# SerialKeyboard.net
KiCad netlist of a schematic drawn in EAGLE
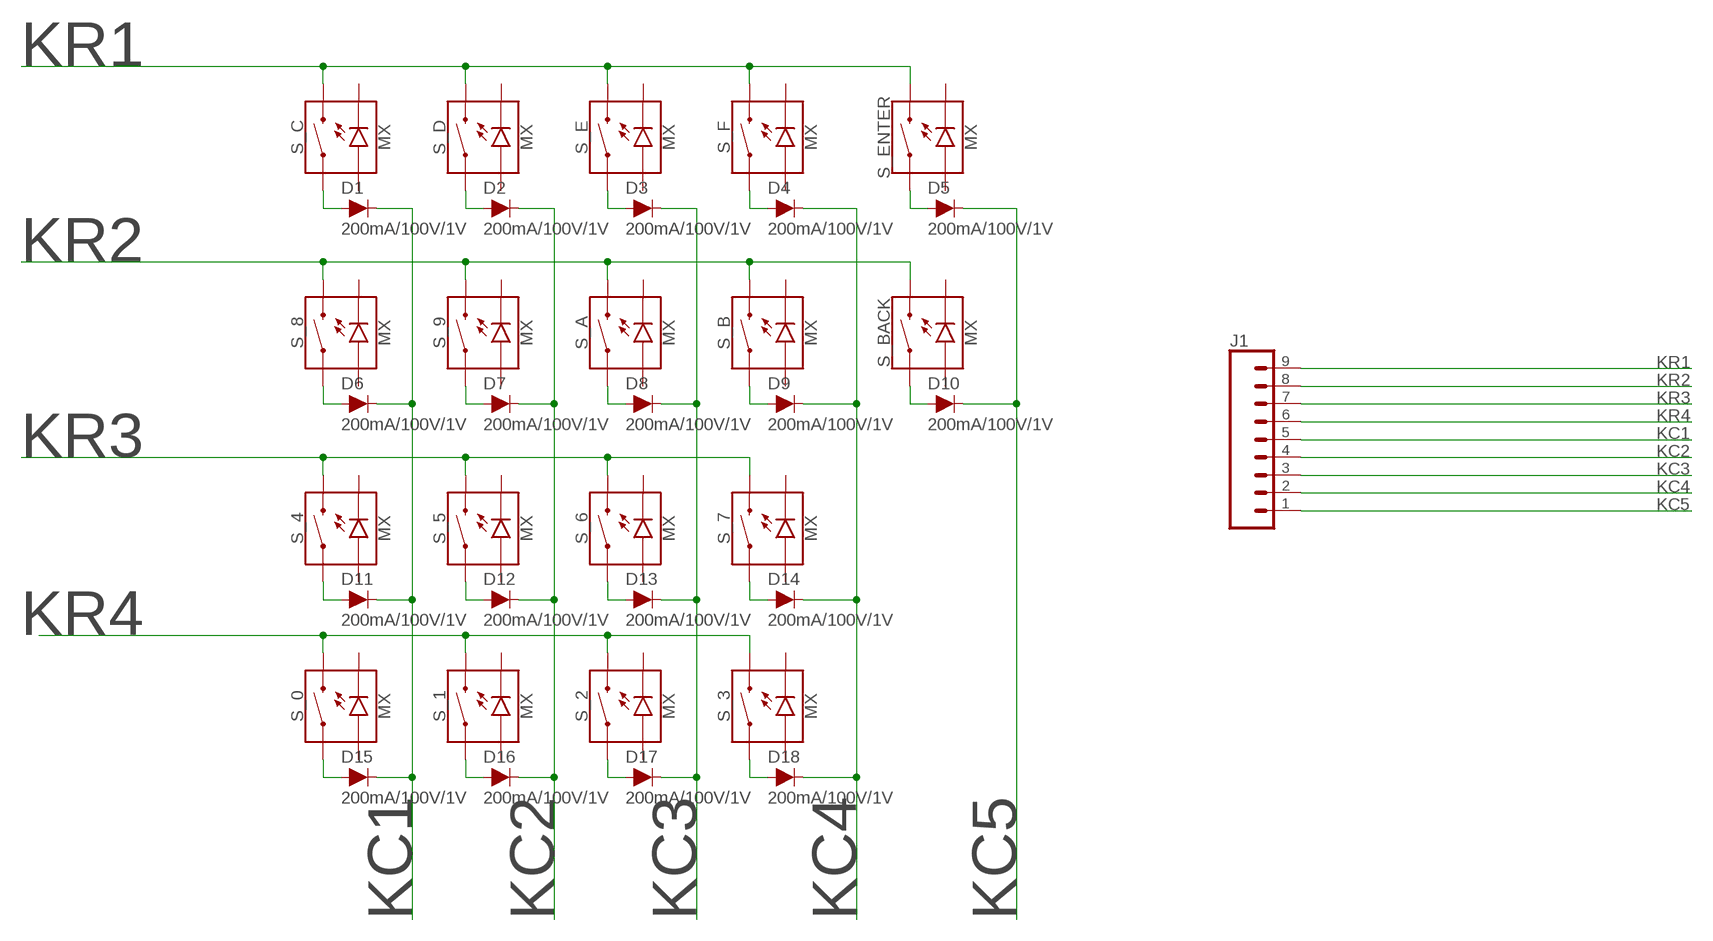
[diagram p0: schematic, sheet 1]

(export (version "E")
  (design (tool "Eeschema 10.0.6"))
  (components
    (comp (ref "D1")
      (value "200mA/100V/1V")
      (footprint "eagle-import:DIODE-1N4148")
      (libsource (lib "eagle-import") (part "DIODE-1N4148"))
    )
    (comp (ref "D2")
      (value "200mA/100V/1V")
      (footprint "eagle-import:DIODE-1N4148")
      (libsource (lib "eagle-import") (part "DIODE-1N4148"))
    )
    (comp (ref "D3")
      (value "200mA/100V/1V")
      (footprint "eagle-import:DIODE-1N4148")
      (libsource (lib "eagle-import") (part "DIODE-1N4148"))
    )
    (comp (ref "D4")
      (value "200mA/100V/1V")
      (footprint "eagle-import:DIODE-1N4148")
      (libsource (lib "eagle-import") (part "DIODE-1N4148"))
    )
    (comp (ref "D5")
      (value "200mA/100V/1V")
      (footprint "eagle-import:DIODE-1N4148")
      (libsource (lib "eagle-import") (part "DIODE-1N4148"))
    )
    (comp (ref "D6")
      (value "200mA/100V/1V")
      (footprint "eagle-import:DIODE-1N4148")
      (libsource (lib "eagle-import") (part "DIODE-1N4148"))
    )
    (comp (ref "D7")
      (value "200mA/100V/1V")
      (footprint "eagle-import:DIODE-1N4148")
      (libsource (lib "eagle-import") (part "DIODE-1N4148"))
    )
    (comp (ref "D8")
      (value "200mA/100V/1V")
      (footprint "eagle-import:DIODE-1N4148")
      (libsource (lib "eagle-import") (part "DIODE-1N4148"))
    )
    (comp (ref "D9")
      (value "200mA/100V/1V")
      (footprint "eagle-import:DIODE-1N4148")
      (libsource (lib "eagle-import") (part "DIODE-1N4148"))
    )
    (comp (ref "D10")
      (value "200mA/100V/1V")
      (footprint "eagle-import:DIODE-1N4148")
      (libsource (lib "eagle-import") (part "DIODE-1N4148"))
    )
    (comp (ref "D11")
      (value "200mA/100V/1V")
      (footprint "eagle-import:DIODE-1N4148")
      (libsource (lib "eagle-import") (part "DIODE-1N4148"))
    )
    (comp (ref "D12")
      (value "200mA/100V/1V")
      (footprint "eagle-import:DIODE-1N4148")
      (libsource (lib "eagle-import") (part "DIODE-1N4148"))
    )
    (comp (ref "D13")
      (value "200mA/100V/1V")
      (footprint "eagle-import:DIODE-1N4148")
      (libsource (lib "eagle-import") (part "DIODE-1N4148"))
    )
    (comp (ref "D14")
      (value "200mA/100V/1V")
      (footprint "eagle-import:DIODE-1N4148")
      (libsource (lib "eagle-import") (part "DIODE-1N4148"))
    )
    (comp (ref "D15")
      (value "200mA/100V/1V")
      (footprint "eagle-import:DIODE-1N4148")
      (libsource (lib "eagle-import") (part "DIODE-1N4148"))
    )
    (comp (ref "D16")
      (value "200mA/100V/1V")
      (footprint "eagle-import:DIODE-1N4148")
      (libsource (lib "eagle-import") (part "DIODE-1N4148"))
    )
    (comp (ref "D17")
      (value "200mA/100V/1V")
      (footprint "eagle-import:DIODE-1N4148")
      (libsource (lib "eagle-import") (part "DIODE-1N4148"))
    )
    (comp (ref "D18")
      (value "200mA/100V/1V")
      (footprint "eagle-import:DIODE-1N4148")
      (libsource (lib "eagle-import") (part "DIODE-1N4148"))
    )
    (comp (ref "J1")
      (value "CONN_09")
      (footprint "eagle-import:1X09")
      (libsource (lib "eagle-import") (part "CONN_09"))
    )
    (comp (ref "S_0")
      (value "MX")
      (footprint "eagle-import:CHERRY-MX-LED")
      (libsource (lib "eagle-import") (part "MOMENTARY-SWITCH-SPST-LED-PTH-CHERRY"))
    )
    (comp (ref "S_1")
      (value "MX")
      (footprint "eagle-import:CHERRY-MX-LED")
      (libsource (lib "eagle-import") (part "MOMENTARY-SWITCH-SPST-LED-PTH-CHERRY"))
    )
    (comp (ref "S_2")
      (value "MX")
      (footprint "eagle-import:CHERRY-MX-LED")
      (libsource (lib "eagle-import") (part "MOMENTARY-SWITCH-SPST-LED-PTH-CHERRY"))
    )
    (comp (ref "S_3")
      (value "MX")
      (footprint "eagle-import:CHERRY-MX-LED")
      (libsource (lib "eagle-import") (part "MOMENTARY-SWITCH-SPST-LED-PTH-CHERRY"))
    )
    (comp (ref "S_4")
      (value "MX")
      (footprint "eagle-import:CHERRY-MX-LED")
      (libsource (lib "eagle-import") (part "MOMENTARY-SWITCH-SPST-LED-PTH-CHERRY"))
    )
    (comp (ref "S_5")
      (value "MX")
      (footprint "eagle-import:CHERRY-MX-LED")
      (libsource (lib "eagle-import") (part "MOMENTARY-SWITCH-SPST-LED-PTH-CHERRY"))
    )
    (comp (ref "S_6")
      (value "MX")
      (footprint "eagle-import:CHERRY-MX-LED")
      (libsource (lib "eagle-import") (part "MOMENTARY-SWITCH-SPST-LED-PTH-CHERRY"))
    )
    (comp (ref "S_7")
      (value "MX")
      (footprint "eagle-import:CHERRY-MX-LED")
      (libsource (lib "eagle-import") (part "MOMENTARY-SWITCH-SPST-LED-PTH-CHERRY"))
    )
    (comp (ref "S_8")
      (value "MX")
      (footprint "eagle-import:CHERRY-MX-LED")
      (libsource (lib "eagle-import") (part "MOMENTARY-SWITCH-SPST-LED-PTH-CHERRY"))
    )
    (comp (ref "S_9")
      (value "MX")
      (footprint "eagle-import:CHERRY-MX-LED")
      (libsource (lib "eagle-import") (part "MOMENTARY-SWITCH-SPST-LED-PTH-CHERRY"))
    )
    (comp (ref "S_A")
      (value "MX")
      (footprint "eagle-import:CHERRY-MX-LED")
      (libsource (lib "eagle-import") (part "MOMENTARY-SWITCH-SPST-LED-PTH-CHERRY"))
    )
    (comp (ref "S_B")
      (value "MX")
      (footprint "eagle-import:CHERRY-MX-LED")
      (libsource (lib "eagle-import") (part "MOMENTARY-SWITCH-SPST-LED-PTH-CHERRY"))
    )
    (comp (ref "S_BACK")
      (value "MX")
      (footprint "eagle-import:CHERRY-MX-LED")
      (libsource (lib "eagle-import") (part "MOMENTARY-SWITCH-SPST-LED-PTH-CHERRY"))
    )
    (comp (ref "S_C")
      (value "MX")
      (footprint "eagle-import:CHERRY-MX-LED")
      (libsource (lib "eagle-import") (part "MOMENTARY-SWITCH-SPST-LED-PTH-CHERRY"))
    )
    (comp (ref "S_D")
      (value "MX")
      (footprint "eagle-import:CHERRY-MX-LED")
      (libsource (lib "eagle-import") (part "MOMENTARY-SWITCH-SPST-LED-PTH-CHERRY"))
    )
    (comp (ref "S_E")
      (value "MX")
      (footprint "eagle-import:CHERRY-MX-LED")
      (libsource (lib "eagle-import") (part "MOMENTARY-SWITCH-SPST-LED-PTH-CHERRY"))
    )
    (comp (ref "S_ENTER")
      (value "MX")
      (footprint "eagle-import:CHERRY-MX-LED")
      (libsource (lib "eagle-import") (part "MOMENTARY-SWITCH-SPST-LED-PTH-CHERRY"))
    )
    (comp (ref "S_F")
      (value "MX")
      (footprint "eagle-import:CHERRY-MX-LED")
      (libsource (lib "eagle-import") (part "MOMENTARY-SWITCH-SPST-LED-PTH-CHERRY"))
    )
  )
  (nets
    (net (code "1") (name "/KC1") (class "Default")
      (node (ref "D1") (pin "C") (pinfunction "C_C") (pintype "passive"))
      (node (ref "D11") (pin "C") (pinfunction "C_C") (pintype "passive"))
      (node (ref "D15") (pin "C") (pinfunction "C_C") (pintype "passive"))
      (node (ref "D6") (pin "C") (pinfunction "C_C") (pintype "passive"))
      (node (ref "J1") (pin "5") (pinfunction "5_5") (pintype "passive"))
    )
    (net (code "2") (name "/KC2") (class "Default")
      (node (ref "D12") (pin "C") (pinfunction "C_C") (pintype "passive"))
      (node (ref "D16") (pin "C") (pinfunction "C_C") (pintype "passive"))
      (node (ref "D2") (pin "C") (pinfunction "C_C") (pintype "passive"))
      (node (ref "D7") (pin "C") (pinfunction "C_C") (pintype "passive"))
      (node (ref "J1") (pin "4") (pinfunction "4_4") (pintype "passive"))
    )
    (net (code "3") (name "/KC3") (class "Default")
      (node (ref "D13") (pin "C") (pinfunction "C_C") (pintype "passive"))
      (node (ref "D17") (pin "C") (pinfunction "C_C") (pintype "passive"))
      (node (ref "D3") (pin "C") (pinfunction "C_C") (pintype "passive"))
      (node (ref "D8") (pin "C") (pinfunction "C_C") (pintype "passive"))
      (node (ref "J1") (pin "3") (pinfunction "3_3") (pintype "passive"))
    )
    (net (code "4") (name "/KC4") (class "Default")
      (node (ref "D14") (pin "C") (pinfunction "C_C") (pintype "passive"))
      (node (ref "D18") (pin "C") (pinfunction "C_C") (pintype "passive"))
      (node (ref "D4") (pin "C") (pinfunction "C_C") (pintype "passive"))
      (node (ref "D9") (pin "C") (pinfunction "C_C") (pintype "passive"))
      (node (ref "J1") (pin "2") (pinfunction "2_2") (pintype "passive"))
    )
    (net (code "5") (name "/KC5") (class "Default")
      (node (ref "D10") (pin "C") (pinfunction "C_C") (pintype "passive"))
      (node (ref "D5") (pin "C") (pinfunction "C_C") (pintype "passive"))
      (node (ref "J1") (pin "1") (pinfunction "1_1") (pintype "passive"))
    )
    (net (code "6") (name "/KR1") (class "Default")
      (node (ref "J1") (pin "9") (pinfunction "9_9") (pintype "passive"))
      (node (ref "S_C") (pin "S2") (pinfunction "2_S2") (pintype "passive"))
      (node (ref "S_D") (pin "S2") (pinfunction "2_S2") (pintype "passive"))
      (node (ref "S_E") (pin "S2") (pinfunction "2_S2") (pintype "passive"))
      (node (ref "S_ENTER") (pin "S2") (pinfunction "2_S2") (pintype "passive"))
      (node (ref "S_F") (pin "S2") (pinfunction "2_S2") (pintype "passive"))
    )
    (net (code "7") (name "/KR2") (class "Default")
      (node (ref "J1") (pin "8") (pinfunction "8_8") (pintype "passive"))
      (node (ref "S_8") (pin "S2") (pinfunction "2_S2") (pintype "passive"))
      (node (ref "S_9") (pin "S2") (pinfunction "2_S2") (pintype "passive"))
      (node (ref "S_A") (pin "S2") (pinfunction "2_S2") (pintype "passive"))
      (node (ref "S_B") (pin "S2") (pinfunction "2_S2") (pintype "passive"))
      (node (ref "S_BACK") (pin "S2") (pinfunction "2_S2") (pintype "passive"))
    )
    (net (code "8") (name "/KR3") (class "Default")
      (node (ref "J1") (pin "7") (pinfunction "7_7") (pintype "passive"))
      (node (ref "S_4") (pin "S2") (pinfunction "2_S2") (pintype "passive"))
      (node (ref "S_5") (pin "S2") (pinfunction "2_S2") (pintype "passive"))
      (node (ref "S_6") (pin "S2") (pinfunction "2_S2") (pintype "passive"))
      (node (ref "S_7") (pin "S2") (pinfunction "2_S2") (pintype "passive"))
    )
    (net (code "9") (name "/KR4") (class "Default")
      (node (ref "J1") (pin "6") (pinfunction "6_6") (pintype "passive"))
      (node (ref "S_0") (pin "S2") (pinfunction "2_S2") (pintype "passive"))
      (node (ref "S_1") (pin "S2") (pinfunction "2_S2") (pintype "passive"))
      (node (ref "S_2") (pin "S2") (pinfunction "2_S2") (pintype "passive"))
      (node (ref "S_3") (pin "S2") (pinfunction "2_S2") (pintype "passive"))
    )
    (net (code "10") (name "Net-(S_0-1)") (class "Default")
      (node (ref "D15") (pin "A") (pinfunction "A_A") (pintype "passive"))
      (node (ref "S_0") (pin "S1") (pinfunction "1_S1") (pintype "passive"))
    )
    (net (code "11") (name "Net-(S_1-1)") (class "Default")
      (node (ref "D16") (pin "A") (pinfunction "A_A") (pintype "passive"))
      (node (ref "S_1") (pin "S1") (pinfunction "1_S1") (pintype "passive"))
    )
    (net (code "12") (name "Net-(S_2-1)") (class "Default")
      (node (ref "D17") (pin "A") (pinfunction "A_A") (pintype "passive"))
      (node (ref "S_2") (pin "S1") (pinfunction "1_S1") (pintype "passive"))
    )
    (net (code "13") (name "Net-(S_3-1)") (class "Default")
      (node (ref "D18") (pin "A") (pinfunction "A_A") (pintype "passive"))
      (node (ref "S_3") (pin "S1") (pinfunction "1_S1") (pintype "passive"))
    )
    (net (code "14") (name "Net-(S_4-1)") (class "Default")
      (node (ref "D11") (pin "A") (pinfunction "A_A") (pintype "passive"))
      (node (ref "S_4") (pin "S1") (pinfunction "1_S1") (pintype "passive"))
    )
    (net (code "15") (name "Net-(S_5-1)") (class "Default")
      (node (ref "D12") (pin "A") (pinfunction "A_A") (pintype "passive"))
      (node (ref "S_5") (pin "S1") (pinfunction "1_S1") (pintype "passive"))
    )
    (net (code "16") (name "Net-(S_6-1)") (class "Default")
      (node (ref "D13") (pin "A") (pinfunction "A_A") (pintype "passive"))
      (node (ref "S_6") (pin "S1") (pinfunction "1_S1") (pintype "passive"))
    )
    (net (code "17") (name "Net-(S_7-1)") (class "Default")
      (node (ref "D14") (pin "A") (pinfunction "A_A") (pintype "passive"))
      (node (ref "S_7") (pin "S1") (pinfunction "1_S1") (pintype "passive"))
    )
    (net (code "18") (name "Net-(S_8-1)") (class "Default")
      (node (ref "D6") (pin "A") (pinfunction "A_A") (pintype "passive"))
      (node (ref "S_8") (pin "S1") (pinfunction "1_S1") (pintype "passive"))
    )
    (net (code "19") (name "Net-(S_9-1)") (class "Default")
      (node (ref "D7") (pin "A") (pinfunction "A_A") (pintype "passive"))
      (node (ref "S_9") (pin "S1") (pinfunction "1_S1") (pintype "passive"))
    )
    (net (code "20") (name "Net-(S_A-1)") (class "Default")
      (node (ref "D8") (pin "A") (pinfunction "A_A") (pintype "passive"))
      (node (ref "S_A") (pin "S1") (pinfunction "1_S1") (pintype "passive"))
    )
    (net (code "21") (name "Net-(S_B-1)") (class "Default")
      (node (ref "D9") (pin "A") (pinfunction "A_A") (pintype "passive"))
      (node (ref "S_B") (pin "S1") (pinfunction "1_S1") (pintype "passive"))
    )
    (net (code "22") (name "Net-(S_BACK-1)") (class "Default")
      (node (ref "D10") (pin "A") (pinfunction "A_A") (pintype "passive"))
      (node (ref "S_BACK") (pin "S1") (pinfunction "1_S1") (pintype "passive"))
    )
    (net (code "23") (name "Net-(S_C-1)") (class "Default")
      (node (ref "D1") (pin "A") (pinfunction "A_A") (pintype "passive"))
      (node (ref "S_C") (pin "S1") (pinfunction "1_S1") (pintype "passive"))
    )
    (net (code "24") (name "Net-(S_D-1)") (class "Default")
      (node (ref "D2") (pin "A") (pinfunction "A_A") (pintype "passive"))
      (node (ref "S_D") (pin "S1") (pinfunction "1_S1") (pintype "passive"))
    )
    (net (code "25") (name "Net-(S_E-1)") (class "Default")
      (node (ref "D3") (pin "A") (pinfunction "A_A") (pintype "passive"))
      (node (ref "S_E") (pin "S1") (pinfunction "1_S1") (pintype "passive"))
    )
    (net (code "26") (name "Net-(S_ENTER-1)") (class "Default")
      (node (ref "D5") (pin "A") (pinfunction "A_A") (pintype "passive"))
      (node (ref "S_ENTER") (pin "S1") (pinfunction "1_S1") (pintype "passive"))
    )
    (net (code "27") (name "Net-(S_F-1)") (class "Default")
      (node (ref "D4") (pin "A") (pinfunction "A_A") (pintype "passive"))
      (node (ref "S_F") (pin "S1") (pinfunction "1_S1") (pintype "passive"))
    )
    (net (code "28") (name "unconnected-(S_0-C-PadK)") (class "Default")
      (node (ref "S_0") (pin "K") (pinfunction "C_K") (pintype "passive"))
    )
    (net (code "29") (name "unconnected-(S_0-PadA)") (class "Default")
      (node (ref "S_0") (pin "A") (pinfunction "A_A") (pintype "passive"))
    )
    (net (code "30") (name "unconnected-(S_1-C-PadK)") (class "Default")
      (node (ref "S_1") (pin "K") (pinfunction "C_K") (pintype "passive"))
    )
    (net (code "31") (name "unconnected-(S_1-PadA)") (class "Default")
      (node (ref "S_1") (pin "A") (pinfunction "A_A") (pintype "passive"))
    )
    (net (code "32") (name "unconnected-(S_2-C-PadK)") (class "Default")
      (node (ref "S_2") (pin "K") (pinfunction "C_K") (pintype "passive"))
    )
    (net (code "33") (name "unconnected-(S_2-PadA)") (class "Default")
      (node (ref "S_2") (pin "A") (pinfunction "A_A") (pintype "passive"))
    )
    (net (code "34") (name "unconnected-(S_3-C-PadK)") (class "Default")
      (node (ref "S_3") (pin "K") (pinfunction "C_K") (pintype "passive"))
    )
    (net (code "35") (name "unconnected-(S_3-PadA)") (class "Default")
      (node (ref "S_3") (pin "A") (pinfunction "A_A") (pintype "passive"))
    )
    (net (code "36") (name "unconnected-(S_4-C-PadK)") (class "Default")
      (node (ref "S_4") (pin "K") (pinfunction "C_K") (pintype "passive"))
    )
    (net (code "37") (name "unconnected-(S_4-PadA)") (class "Default")
      (node (ref "S_4") (pin "A") (pinfunction "A_A") (pintype "passive"))
    )
    (net (code "38") (name "unconnected-(S_5-C-PadK)") (class "Default")
      (node (ref "S_5") (pin "K") (pinfunction "C_K") (pintype "passive"))
    )
    (net (code "39") (name "unconnected-(S_5-PadA)") (class "Default")
      (node (ref "S_5") (pin "A") (pinfunction "A_A") (pintype "passive"))
    )
    (net (code "40") (name "unconnected-(S_6-C-PadK)") (class "Default")
      (node (ref "S_6") (pin "K") (pinfunction "C_K") (pintype "passive"))
    )
    (net (code "41") (name "unconnected-(S_6-PadA)") (class "Default")
      (node (ref "S_6") (pin "A") (pinfunction "A_A") (pintype "passive"))
    )
    (net (code "42") (name "unconnected-(S_7-C-PadK)") (class "Default")
      (node (ref "S_7") (pin "K") (pinfunction "C_K") (pintype "passive"))
    )
    (net (code "43") (name "unconnected-(S_7-PadA)") (class "Default")
      (node (ref "S_7") (pin "A") (pinfunction "A_A") (pintype "passive"))
    )
    (net (code "44") (name "unconnected-(S_8-C-PadK)") (class "Default")
      (node (ref "S_8") (pin "K") (pinfunction "C_K") (pintype "passive"))
    )
    (net (code "45") (name "unconnected-(S_8-PadA)") (class "Default")
      (node (ref "S_8") (pin "A") (pinfunction "A_A") (pintype "passive"))
    )
    (net (code "46") (name "unconnected-(S_9-C-PadK)") (class "Default")
      (node (ref "S_9") (pin "K") (pinfunction "C_K") (pintype "passive"))
    )
    (net (code "47") (name "unconnected-(S_9-PadA)") (class "Default")
      (node (ref "S_9") (pin "A") (pinfunction "A_A") (pintype "passive"))
    )
    (net (code "48") (name "unconnected-(S_A-C-PadK)") (class "Default")
      (node (ref "S_A") (pin "K") (pinfunction "C_K") (pintype "passive"))
    )
    (net (code "49") (name "unconnected-(S_A-PadA)") (class "Default")
      (node (ref "S_A") (pin "A") (pinfunction "A_A") (pintype "passive"))
    )
    (net (code "50") (name "unconnected-(S_B-C-PadK)") (class "Default")
      (node (ref "S_B") (pin "K") (pinfunction "C_K") (pintype "passive"))
    )
    (net (code "51") (name "unconnected-(S_B-PadA)") (class "Default")
      (node (ref "S_B") (pin "A") (pinfunction "A_A") (pintype "passive"))
    )
    (net (code "52") (name "unconnected-(S_BACK-C-PadK)") (class "Default")
      (node (ref "S_BACK") (pin "K") (pinfunction "C_K") (pintype "passive"))
    )
    (net (code "53") (name "unconnected-(S_BACK-PadA)") (class "Default")
      (node (ref "S_BACK") (pin "A") (pinfunction "A_A") (pintype "passive"))
    )
    (net (code "54") (name "unconnected-(S_C-C-PadK)") (class "Default")
      (node (ref "S_C") (pin "K") (pinfunction "C_K") (pintype "passive"))
    )
    (net (code "55") (name "unconnected-(S_C-PadA)") (class "Default")
      (node (ref "S_C") (pin "A") (pinfunction "A_A") (pintype "passive"))
    )
    (net (code "56") (name "unconnected-(S_D-C-PadK)") (class "Default")
      (node (ref "S_D") (pin "K") (pinfunction "C_K") (pintype "passive"))
    )
    (net (code "57") (name "unconnected-(S_D-PadA)") (class "Default")
      (node (ref "S_D") (pin "A") (pinfunction "A_A") (pintype "passive"))
    )
    (net (code "58") (name "unconnected-(S_E-C-PadK)") (class "Default")
      (node (ref "S_E") (pin "K") (pinfunction "C_K") (pintype "passive"))
    )
    (net (code "59") (name "unconnected-(S_E-PadA)") (class "Default")
      (node (ref "S_E") (pin "A") (pinfunction "A_A") (pintype "passive"))
    )
    (net (code "60") (name "unconnected-(S_ENTER-C-PadK)") (class "Default")
      (node (ref "S_ENTER") (pin "K") (pinfunction "C_K") (pintype "passive"))
    )
    (net (code "61") (name "unconnected-(S_ENTER-PadA)") (class "Default")
      (node (ref "S_ENTER") (pin "A") (pinfunction "A_A") (pintype "passive"))
    )
    (net (code "62") (name "unconnected-(S_F-C-PadK)") (class "Default")
      (node (ref "S_F") (pin "K") (pinfunction "C_K") (pintype "passive"))
    )
    (net (code "63") (name "unconnected-(S_F-PadA)") (class "Default")
      (node (ref "S_F") (pin "A") (pinfunction "A_A") (pintype "passive"))
    )
  )
)
